# 3phasecntrl-rev2.net
KiCad netlist of a schematic drawn in EAGLE
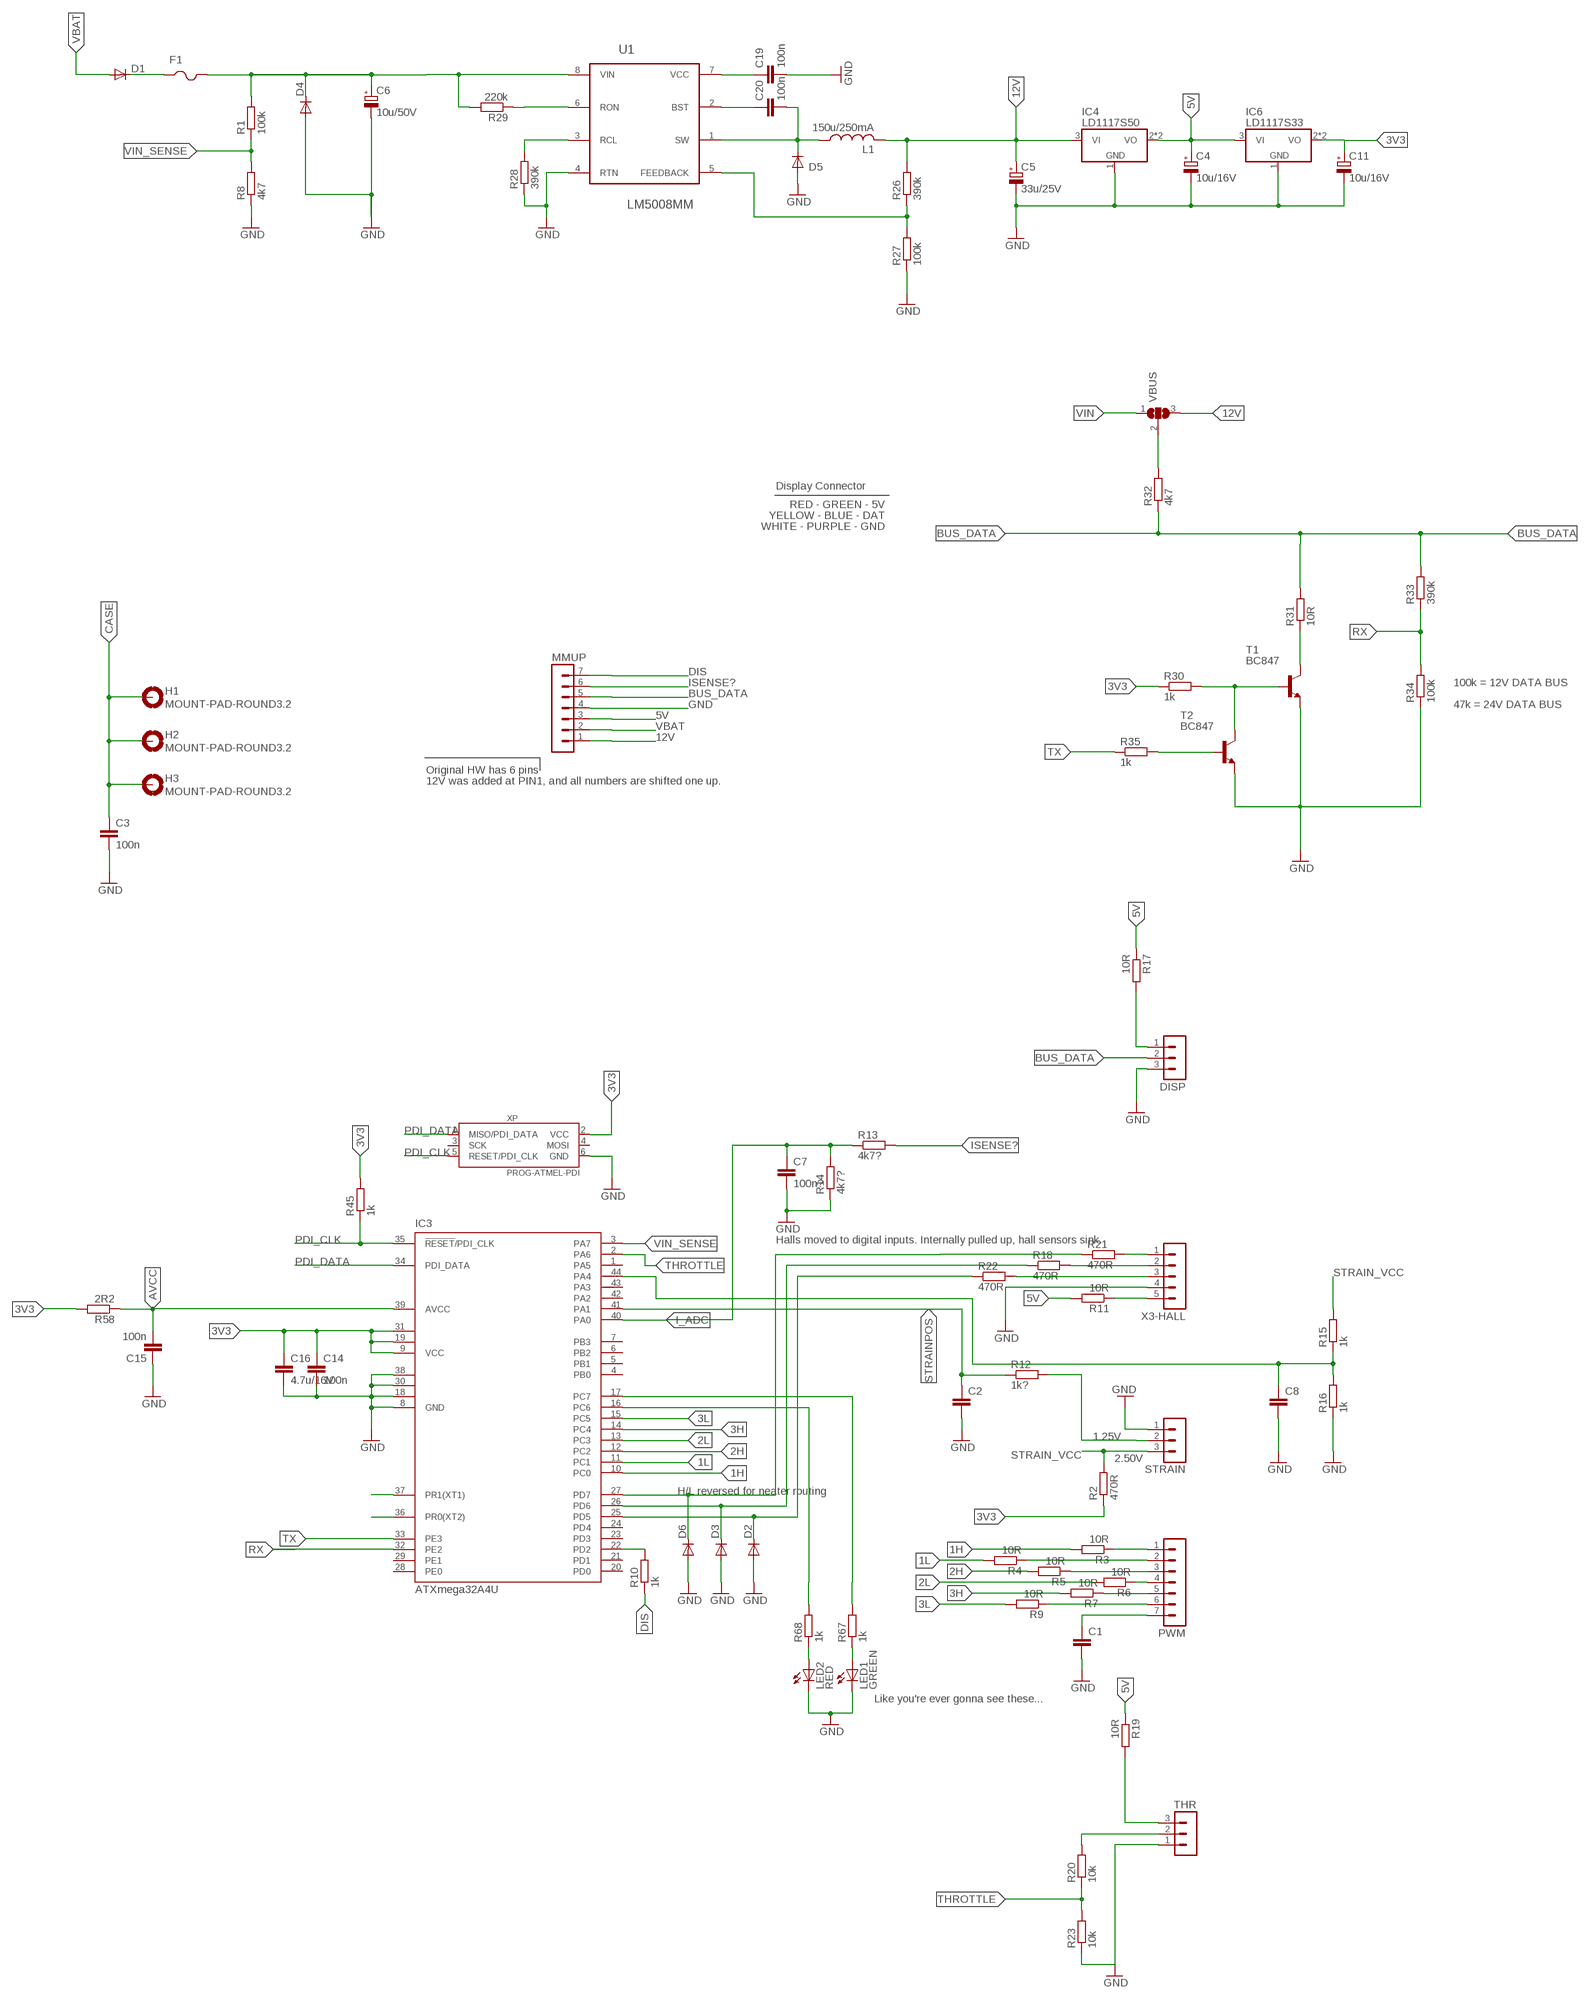
[diagram p0: schematic, sheet 1]

(export (version "E")
  (design (tool "Eeschema 10.0.6"))
  (components
    (comp (ref "C1")
      (value "C-EUC0805K")
      (footprint "eagle-import:C0805K")
      (libsource (lib "eagle-import") (part "C-EUC0805K"))
    )
    (comp (ref "C2")
      (value "C-EUC0805K")
      (footprint "eagle-import:C0805K")
      (libsource (lib "eagle-import") (part "C-EUC0805K"))
    )
    (comp (ref "C3")
      (value "100n")
      (footprint "eagle-import:C0805K")
      (libsource (lib "eagle-import") (part "C-EUC0805K"))
    )
    (comp (ref "C4")
      (value "10u/16V")
      (footprint "eagle-import:153CLV-0405")
      (libsource (lib "eagle-import") (part "CPOL-EU153CLV-0405"))
    )
    (comp (ref "C5")
      (value "33u/25V")
      (footprint "eagle-import:153CLV-0605")
      (libsource (lib "eagle-import") (part "CPOL-EU153CLV-0605"))
    )
    (comp (ref "C6")
      (value "10u/50V")
      (footprint "eagle-import:153CLV-0605")
      (libsource (lib "eagle-import") (part "CPOL-EU153CLV-0605"))
    )
    (comp (ref "C7")
      (value "100n?")
      (footprint "eagle-import:C0805K")
      (libsource (lib "eagle-import") (part "C-EUC0805K"))
    )
    (comp (ref "C8")
      (value "C-EUC0805K")
      (footprint "eagle-import:C0805K")
      (libsource (lib "eagle-import") (part "C-EUC0805K"))
    )
    (comp (ref "C11")
      (value "10u/16V")
      (footprint "eagle-import:153CLV-0405")
      (libsource (lib "eagle-import") (part "CPOL-EU153CLV-0405"))
    )
    (comp (ref "C14")
      (value "100n")
      (footprint "eagle-import:C0805K")
      (libsource (lib "eagle-import") (part "C-EUC0805K"))
    )
    (comp (ref "C15")
      (value "100n")
      (footprint "eagle-import:C0805K")
      (libsource (lib "eagle-import") (part "C-EUC0805K"))
    )
    (comp (ref "C16")
      (value "4.7u/16V")
      (footprint "eagle-import:C0805K")
      (libsource (lib "eagle-import") (part "C-EUC0805K"))
    )
    (comp (ref "C19")
      (value "100n")
      (footprint "eagle-import:C0805K")
      (libsource (lib "eagle-import") (part "C-EUC0805K"))
    )
    (comp (ref "C20")
      (value "100n")
      (footprint "eagle-import:C0805K")
      (libsource (lib "eagle-import") (part "C-EUC0805K"))
    )
    (comp (ref "D1")
      (value "BAT46WH")
      (footprint "eagle-import:SMB")
      (libsource (lib "eagle-import") (part "DIODE-SMB"))
    )
    (comp (ref "D2")
      (value "PTVS3V3S1UTR")
      (footprint "eagle-import:SOD123")
      (libsource (lib "eagle-import") (part "DIODE-SOD123"))
    )
    (comp (ref "D3")
      (value "PTVS3V3S1UTR")
      (footprint "eagle-import:SOD123")
      (libsource (lib "eagle-import") (part "DIODE-SOD123"))
    )
    (comp (ref "D4")
      (value "SM6T39A")
      (footprint "eagle-import:SMB")
      (libsource (lib "eagle-import") (part "DIODE-SMB"))
    )
    (comp (ref "D5")
      (value "BAT46WH")
      (footprint "eagle-import:SOD323-W")
      (libsource (lib "eagle-import") (part "DIODE-SOD323-W"))
    )
    (comp (ref "D6")
      (value "PTVS3V3S1UTR")
      (footprint "eagle-import:SOD123")
      (libsource (lib "eagle-import") (part "DIODE-SOD123"))
    )
    (comp (ref "DISP")
      (value "MA03-1")
      (footprint "eagle-import:MA03-1")
      (fields (field (name "OC_FARNELL") "unknown") (field (name "OC_NEWARK") "unknown"))
      (libsource (lib "eagle-import") (part "MA03-1"))
    )
    (comp (ref "F1")
      (value "PTCFUSE-1812")
      (footprint "eagle-import:1812")
      (libsource (lib "eagle-import") (part "PTCFUSE-1812"))
    )
    (comp (ref "H1")
      (value "MOUNT-PAD-ROUND3.2")
      (footprint "eagle-import:3,2-PAD")
      (libsource (lib "eagle-import") (part "MOUNT-PAD-ROUND3.2"))
    )
    (comp (ref "H2")
      (value "MOUNT-PAD-ROUND3.2")
      (footprint "eagle-import:3,2-PAD")
      (libsource (lib "eagle-import") (part "MOUNT-PAD-ROUND3.2"))
    )
    (comp (ref "H3")
      (value "MOUNT-PAD-ROUND3.2")
      (footprint "eagle-import:3,2-PAD")
      (libsource (lib "eagle-import") (part "MOUNT-PAD-ROUND3.2"))
    )
    (comp (ref "IC3")
      (value "ATXmega32A4U")
      (footprint "eagle-import:TQFP44")
      (libsource (lib "eagle-import") (part "XMEGA16A4A"))
    )
    (comp (ref "IC4")
      (value "LD1117S50")
      (footprint "eagle-import:SOT223")
      (libsource (lib "eagle-import") (part "LM340?-STST"))
    )
    (comp (ref "IC6")
      (value "LD1117S33")
      (footprint "eagle-import:SOT223")
      (libsource (lib "eagle-import") (part "LM340?-STST"))
    )
    (comp (ref "L1")
      (value "150u/250mA")
      (footprint "eagle-import:POWER-CHOKE_WE-TPC")
      (libsource (lib "eagle-import") (part "L-USWE-TPC"))
    )
    (comp (ref "LED1")
      (value "GREEN")
      (footprint "eagle-import:CHIPLED_0805")
      (libsource (lib "eagle-import") (part "LEDCHIPLED_0805"))
    )
    (comp (ref "LED2")
      (value "RED")
      (footprint "eagle-import:CHIPLED_0805")
      (libsource (lib "eagle-import") (part "LEDCHIPLED_0805"))
    )
    (comp (ref "MMUP")
      (value "MA07-1")
      (footprint "eagle-import:MA07-1")
      (fields (field (name "OC_FARNELL") "unknown") (field (name "OC_NEWARK") "unknown"))
      (libsource (lib "eagle-import") (part "MA07-1"))
    )
    (comp (ref "PWM")
      (value "MA07-1")
      (footprint "eagle-import:MA07-1")
      (libsource (lib "eagle-import") (part "MA07-1"))
    )
    (comp (ref "R1")
      (value "100k")
      (footprint "eagle-import:M0805")
      (libsource (lib "eagle-import") (part "R-EU_M0805"))
    )
    (comp (ref "R2")
      (value "470R")
      (footprint "eagle-import:M0805")
      (libsource (lib "eagle-import") (part "R-EU_M0805"))
    )
    (comp (ref "R3")
      (value "10R")
      (footprint "eagle-import:M0805")
      (libsource (lib "eagle-import") (part "R-EU_M0805"))
    )
    (comp (ref "R4")
      (value "10R")
      (footprint "eagle-import:M0805")
      (libsource (lib "eagle-import") (part "R-EU_M0805"))
    )
    (comp (ref "R5")
      (value "10R")
      (footprint "eagle-import:M0805")
      (libsource (lib "eagle-import") (part "R-EU_M0805"))
    )
    (comp (ref "R6")
      (value "10R")
      (footprint "eagle-import:M0805")
      (libsource (lib "eagle-import") (part "R-EU_M0805"))
    )
    (comp (ref "R7")
      (value "10R")
      (footprint "eagle-import:M0805")
      (libsource (lib "eagle-import") (part "R-EU_M0805"))
    )
    (comp (ref "R8")
      (value "4k7")
      (footprint "eagle-import:M0805")
      (libsource (lib "eagle-import") (part "R-EU_M0805"))
    )
    (comp (ref "R9")
      (value "10R")
      (footprint "eagle-import:M0805")
      (libsource (lib "eagle-import") (part "R-EU_M0805"))
    )
    (comp (ref "R10")
      (value "1k")
      (footprint "eagle-import:M0805")
      (libsource (lib "eagle-import") (part "R-EU_M0805"))
    )
    (comp (ref "R11")
      (value "10R")
      (footprint "eagle-import:M0805")
      (libsource (lib "eagle-import") (part "R-EU_M0805"))
    )
    (comp (ref "R12")
      (value "1k?")
      (footprint "eagle-import:M0805")
      (libsource (lib "eagle-import") (part "R-EU_M0805"))
    )
    (comp (ref "R13")
      (value "4k7?")
      (footprint "eagle-import:M0805")
      (libsource (lib "eagle-import") (part "R-EU_M0805"))
    )
    (comp (ref "R14")
      (value "4k7?")
      (footprint "eagle-import:M0805")
      (libsource (lib "eagle-import") (part "R-EU_M0805"))
    )
    (comp (ref "R15")
      (value "1k")
      (footprint "eagle-import:M0805")
      (libsource (lib "eagle-import") (part "R-EU_M0805"))
    )
    (comp (ref "R16")
      (value "1k")
      (footprint "eagle-import:M0805")
      (libsource (lib "eagle-import") (part "R-EU_M0805"))
    )
    (comp (ref "R17")
      (value "10R")
      (footprint "eagle-import:M0805")
      (libsource (lib "eagle-import") (part "R-EU_M0805"))
    )
    (comp (ref "R18")
      (value "470R")
      (footprint "eagle-import:M0805")
      (libsource (lib "eagle-import") (part "R-EU_M0805"))
    )
    (comp (ref "R19")
      (value "10R")
      (footprint "eagle-import:M0805")
      (libsource (lib "eagle-import") (part "R-EU_M0805"))
    )
    (comp (ref "R20")
      (value "10k")
      (footprint "eagle-import:M0805")
      (libsource (lib "eagle-import") (part "R-EU_M0805"))
    )
    (comp (ref "R21")
      (value "470R")
      (footprint "eagle-import:M0805")
      (libsource (lib "eagle-import") (part "R-EU_M0805"))
    )
    (comp (ref "R22")
      (value "470R")
      (footprint "eagle-import:M0805")
      (libsource (lib "eagle-import") (part "R-EU_M0805"))
    )
    (comp (ref "R23")
      (value "10k")
      (footprint "eagle-import:M0805")
      (libsource (lib "eagle-import") (part "R-EU_M0805"))
    )
    (comp (ref "R26")
      (value "390k")
      (footprint "eagle-import:M0805")
      (libsource (lib "eagle-import") (part "R-EU_M0805"))
    )
    (comp (ref "R27")
      (value "100k")
      (footprint "eagle-import:M0805")
      (libsource (lib "eagle-import") (part "R-EU_M0805"))
    )
    (comp (ref "R28")
      (value "390k")
      (footprint "eagle-import:M0805")
      (libsource (lib "eagle-import") (part "R-EU_M0805"))
    )
    (comp (ref "R29")
      (value "220k")
      (footprint "eagle-import:M0805")
      (libsource (lib "eagle-import") (part "R-EU_M0805"))
    )
    (comp (ref "R30")
      (value "1k")
      (footprint "eagle-import:M0805")
      (libsource (lib "eagle-import") (part "R-EU_M0805"))
    )
    (comp (ref "R31")
      (value "10R")
      (footprint "eagle-import:M0805")
      (libsource (lib "eagle-import") (part "R-EU_M0805"))
    )
    (comp (ref "R32")
      (value "4k7")
      (footprint "eagle-import:M0805")
      (libsource (lib "eagle-import") (part "R-EU_M0805"))
    )
    (comp (ref "R33")
      (value "390k")
      (footprint "eagle-import:M0805")
      (libsource (lib "eagle-import") (part "R-EU_M0805"))
    )
    (comp (ref "R34")
      (value "100k")
      (footprint "eagle-import:M0805")
      (libsource (lib "eagle-import") (part "R-EU_M0805"))
    )
    (comp (ref "R35")
      (value "1k")
      (footprint "eagle-import:M0805")
      (libsource (lib "eagle-import") (part "R-EU_M0805"))
    )
    (comp (ref "R45")
      (value "1k")
      (footprint "eagle-import:R0805")
      (libsource (lib "eagle-import") (part "R-EU_R0805"))
    )
    (comp (ref "R58")
      (value "2R2")
      (footprint "eagle-import:R0805")
      (libsource (lib "eagle-import") (part "R-EU_R0805"))
    )
    (comp (ref "R67")
      (value "1k")
      (footprint "eagle-import:M0805")
      (libsource (lib "eagle-import") (part "R-EU_M0805"))
    )
    (comp (ref "R68")
      (value "1k")
      (footprint "eagle-import:M0805")
      (libsource (lib "eagle-import") (part "R-EU_M0805"))
    )
    (comp (ref "STRAIN")
      (value "MA03-1")
      (footprint "eagle-import:MA03-1")
      (libsource (lib "eagle-import") (part "MA03-1"))
    )
    (comp (ref "T1")
      (value "BC847")
      (footprint "eagle-import:SOT23")
      (libsource (lib "eagle-import") (part "BC847"))
    )
    (comp (ref "T2")
      (value "BC847")
      (footprint "eagle-import:SOT23")
      (libsource (lib "eagle-import") (part "BC847"))
    )
    (comp (ref "THR")
      (value "MA03-1")
      (footprint "eagle-import:MA03-1")
      (libsource (lib "eagle-import") (part "MA03-1"))
    )
    (comp (ref "U1")
      (value "LM5008MM")
      (footprint "eagle-import:SOP65P490X109-8N")
      (libsource (lib "eagle-import") (part "LM5008MM"))
    )
    (comp (ref "VBUS")
      (value "SJ2W")
      (footprint "eagle-import:SJ_2")
      (libsource (lib "eagle-import") (part "SJ2W"))
    )
    (comp (ref "X3-HALL")
      (value "MA05-1")
      (footprint "eagle-import:MA05-1")
      (libsource (lib "eagle-import") (part "MA05-1"))
    )
    (comp (ref "XP")
      (value "PROG-ATMEL-PDI")
      (footprint "eagle-import:6-LSTB2")
      (libsource (lib "eagle-import") (part "PROG-ATMEL-PDI"))
    )
  )
  (nets
    (net (code "1") (name "/PDI_CLK") (class "Default")
      (node (ref "IC3") (pin "35") (pinfunction "~{RESET}/PDI_CLK_35") (pintype "bidirectional"))
      (node (ref "R45") (pin "1") (pinfunction "1_1") (pintype "passive"))
      (node (ref "XP") (pin "5") (pinfunction "RESET/PDI_CLK_5") (pintype "bidirectional"))
    )
    (net (code "2") (name "/PDI_DATA") (class "Default")
      (node (ref "IC3") (pin "34") (pinfunction "PDI_DATA_34") (pintype "bidirectional"))
      (node (ref "XP") (pin "1") (pinfunction "MISO/PDI_DATA_1") (pintype "bidirectional"))
    )
    (net (code "3") (name "/STRAIN_VCC") (class "Default")
      (node (ref "R15") (pin "2") (pinfunction "2_2") (pintype "passive"))
      (node (ref "R2") (pin "2") (pinfunction "2_2") (pintype "passive"))
      (node (ref "STRAIN") (pin "3") (pinfunction "3_3") (pintype "passive"))
    )
    (net (code "4") (name "1H") (class "Default")
      (node (ref "IC3") (pin "10") (pinfunction "PC0_10") (pintype "bidirectional"))
      (node (ref "R3") (pin "2") (pinfunction "2_2") (pintype "passive"))
    )
    (net (code "5") (name "1L") (class "Default")
      (node (ref "IC3") (pin "11") (pinfunction "PC1_11") (pintype "bidirectional"))
      (node (ref "R4") (pin "2") (pinfunction "2_2") (pintype "passive"))
    )
    (net (code "6") (name "2H") (class "Default")
      (node (ref "IC3") (pin "12") (pinfunction "PC2_12") (pintype "bidirectional"))
      (node (ref "R5") (pin "2") (pinfunction "2_2") (pintype "passive"))
    )
    (net (code "7") (name "2L") (class "Default")
      (node (ref "IC3") (pin "13") (pinfunction "PC3_13") (pintype "bidirectional"))
      (node (ref "R6") (pin "2") (pinfunction "2_2") (pintype "passive"))
    )
    (net (code "8") (name "3H") (class "Default")
      (node (ref "IC3") (pin "14") (pinfunction "PC4_14") (pintype "bidirectional"))
      (node (ref "R7") (pin "2") (pinfunction "2_2") (pintype "passive"))
    )
    (net (code "9") (name "3L") (class "Default")
      (node (ref "IC3") (pin "15") (pinfunction "PC5_15") (pintype "bidirectional"))
      (node (ref "R9") (pin "2") (pinfunction "2_2") (pintype "passive"))
    )
    (net (code "10") (name "3V3") (class "Default")
      (node (ref "C11") (pin "+") (pinfunction "+_+") (pintype "passive"))
      (node (ref "C14") (pin "1") (pinfunction "1_1") (pintype "passive"))
      (node (ref "C16") (pin "1") (pinfunction "1_1") (pintype "passive"))
      (node (ref "IC3") (pin "19") (pinfunction "VCC1_19") (pintype "power_in"))
      (node (ref "IC3") (pin "31") (pinfunction "VCC2_31") (pintype "power_in"))
      (node (ref "IC3") (pin "9") (pinfunction "VCC_9") (pintype "power_in"))
      (node (ref "IC6") (pin "2") (pinfunction "VO_2") (pintype "passive"))
      (node (ref "IC6") (pin "4") (pinfunction "VO_4") (pintype "passive"))
      (node (ref "R2") (pin "1") (pinfunction "1_1") (pintype "passive"))
      (node (ref "R30") (pin "1") (pinfunction "1_1") (pintype "passive"))
      (node (ref "R45") (pin "2") (pinfunction "2_2") (pintype "passive"))
      (node (ref "R58") (pin "2") (pinfunction "2_2") (pintype "passive"))
      (node (ref "XP") (pin "2") (pinfunction "VCC_2") (pintype "bidirectional"))
    )
    (net (code "11") (name "5V") (class "Default")
      (node (ref "C4") (pin "+") (pinfunction "+_+") (pintype "passive"))
      (node (ref "IC4") (pin "2") (pinfunction "VO_2") (pintype "passive"))
      (node (ref "IC4") (pin "4") (pinfunction "VO_4") (pintype "passive"))
      (node (ref "IC6") (pin "3") (pinfunction "VI_3") (pintype "input"))
      (node (ref "MMUP") (pin "3") (pinfunction "3_3") (pintype "passive"))
      (node (ref "R11") (pin "2") (pinfunction "2_2") (pintype "passive"))
      (node (ref "R17") (pin "1") (pinfunction "1_1") (pintype "passive"))
      (node (ref "R19") (pin "1") (pinfunction "1_1") (pintype "passive"))
    )
    (net (code "12") (name "12V") (class "Default")
      (node (ref "C5") (pin "+") (pinfunction "+_+") (pintype "passive"))
      (node (ref "IC4") (pin "3") (pinfunction "VI_3") (pintype "input"))
      (node (ref "L1") (pin "2") (pinfunction "2_2") (pintype "passive"))
      (node (ref "MMUP") (pin "1") (pinfunction "1_1") (pintype "passive"))
      (node (ref "R26") (pin "2") (pinfunction "2_2") (pintype "passive"))
      (node (ref "VBUS") (pin "3") (pinfunction "3_3") (pintype "passive"))
    )
    (net (code "13") (name "AVCC") (class "Default")
      (node (ref "C15") (pin "2") (pinfunction "2_2") (pintype "passive"))
      (node (ref "IC3") (pin "39") (pinfunction "AVCC_39") (pintype "power_in"))
      (node (ref "R58") (pin "1") (pinfunction "1_1") (pintype "passive"))
    )
    (net (code "14") (name "BUS_DATA") (class "Default")
      (node (ref "DISP") (pin "2") (pinfunction "2_2") (pintype "passive"))
      (node (ref "MMUP") (pin "5") (pinfunction "5_5") (pintype "passive"))
      (node (ref "R31") (pin "2") (pinfunction "2_2") (pintype "passive"))
      (node (ref "R32") (pin "1") (pinfunction "1_1") (pintype "passive"))
      (node (ref "R33") (pin "2") (pinfunction "2_2") (pintype "passive"))
    )
    (net (code "15") (name "CASE") (class "Default")
      (node (ref "C3") (pin "1") (pinfunction "1_1") (pintype "passive"))
      (node (ref "H1") (pin "B3,2") (pinfunction "MOUNT_B3,2") (pintype "passive"))
      (node (ref "H2") (pin "B3,2") (pinfunction "MOUNT_B3,2") (pintype "passive"))
      (node (ref "H3") (pin "B3,2") (pinfunction "MOUNT_B3,2") (pintype "passive"))
    )
    (net (code "16") (name "DIS") (class "Default")
      (node (ref "MMUP") (pin "7") (pinfunction "7_7") (pintype "passive"))
      (node (ref "R10") (pin "1") (pinfunction "1_1") (pintype "passive"))
    )
    (net (code "17") (name "GND") (class "Default")
      (node (ref "C1") (pin "2") (pinfunction "2_2") (pintype "passive"))
      (node (ref "C11") (pin "-") (pinfunction "-_-") (pintype "passive"))
      (node (ref "C14") (pin "2") (pinfunction "2_2") (pintype "passive"))
      (node (ref "C15") (pin "1") (pinfunction "1_1") (pintype "passive"))
      (node (ref "C16") (pin "2") (pinfunction "2_2") (pintype "passive"))
      (node (ref "C19") (pin "2") (pinfunction "2_2") (pintype "passive"))
      (node (ref "C2") (pin "2") (pinfunction "2_2") (pintype "passive"))
      (node (ref "C3") (pin "2") (pinfunction "2_2") (pintype "passive"))
      (node (ref "C4") (pin "-") (pinfunction "-_-") (pintype "passive"))
      (node (ref "C5") (pin "-") (pinfunction "-_-") (pintype "passive"))
      (node (ref "C6") (pin "-") (pinfunction "-_-") (pintype "passive"))
      (node (ref "C7") (pin "2") (pinfunction "2_2") (pintype "passive"))
      (node (ref "C8") (pin "2") (pinfunction "2_2") (pintype "passive"))
      (node (ref "D2") (pin "A") (pinfunction "A_A") (pintype "passive"))
      (node (ref "D3") (pin "A") (pinfunction "A_A") (pintype "passive"))
      (node (ref "D4") (pin "A") (pinfunction "A_A") (pintype "passive"))
      (node (ref "D5") (pin "A") (pinfunction "A_A") (pintype "passive"))
      (node (ref "D6") (pin "A") (pinfunction "A_A") (pintype "passive"))
      (node (ref "DISP") (pin "3") (pinfunction "3_3") (pintype "passive"))
      (node (ref "IC3") (pin "18") (pinfunction "GND1_18") (pintype "power_in"))
      (node (ref "IC3") (pin "30") (pinfunction "GND2_30") (pintype "power_in"))
      (node (ref "IC3") (pin "38") (pinfunction "GND3_38") (pintype "power_in"))
      (node (ref "IC3") (pin "8") (pinfunction "GND_8") (pintype "power_in"))
      (node (ref "IC4") (pin "1") (pinfunction "GND_1") (pintype "passive"))
      (node (ref "IC6") (pin "1") (pinfunction "GND_1") (pintype "passive"))
      (node (ref "LED1") (pin "C") (pinfunction "C_C") (pintype "passive"))
      (node (ref "LED2") (pin "C") (pinfunction "C_C") (pintype "passive"))
      (node (ref "MMUP") (pin "4") (pinfunction "4_4") (pintype "passive"))
      (node (ref "R14") (pin "1") (pinfunction "1_1") (pintype "passive"))
      (node (ref "R16") (pin "1") (pinfunction "1_1") (pintype "passive"))
      (node (ref "R23") (pin "1") (pinfunction "1_1") (pintype "passive"))
      (node (ref "R27") (pin "1") (pinfunction "1_1") (pintype "passive"))
      (node (ref "R28") (pin "1") (pinfunction "1_1") (pintype "passive"))
      (node (ref "R34") (pin "1") (pinfunction "1_1") (pintype "passive"))
      (node (ref "R8") (pin "1") (pinfunction "1_1") (pintype "passive"))
      (node (ref "STRAIN") (pin "1") (pinfunction "1_1") (pintype "passive"))
      (node (ref "T1") (pin "2") (pinfunction "E_2") (pintype "passive"))
      (node (ref "T2") (pin "2") (pinfunction "E_2") (pintype "passive"))
      (node (ref "THR") (pin "1") (pinfunction "1_1") (pintype "passive"))
      (node (ref "U1") (pin "4") (pinfunction "RTN_4") (pintype "passive"))
      (node (ref "X3-HALL") (pin "4") (pinfunction "4_4") (pintype "passive"))
      (node (ref "XP") (pin "6") (pinfunction "GND_6") (pintype "bidirectional"))
    )
    (net (code "18") (name "ISENSE?") (class "Default")
      (node (ref "MMUP") (pin "6") (pinfunction "6_6") (pintype "passive"))
      (node (ref "R13") (pin "2") (pinfunction "2_2") (pintype "passive"))
    )
    (net (code "19") (name "I_ADC") (class "Default")
      (node (ref "C7") (pin "1") (pinfunction "1_1") (pintype "passive"))
      (node (ref "IC3") (pin "40") (pinfunction "PA0_40") (pintype "bidirectional"))
      (node (ref "R13") (pin "1") (pinfunction "1_1") (pintype "passive"))
      (node (ref "R14") (pin "2") (pinfunction "2_2") (pintype "passive"))
    )
    (net (code "20") (name "Net-(C1-Pad1)") (class "Default")
      (node (ref "C1") (pin "1") (pinfunction "1_1") (pintype "passive"))
      (node (ref "PWM") (pin "7") (pinfunction "7_7") (pintype "passive"))
    )
    (net (code "21") (name "Net-(D1-PadC)") (class "Default")
      (node (ref "D1") (pin "C") (pinfunction "C_C") (pintype "passive"))
      (node (ref "F1") (pin "1") (pinfunction "1_1") (pintype "passive"))
    )
    (net (code "22") (name "Net-(DISP-Pad1)") (class "Default")
      (node (ref "DISP") (pin "1") (pinfunction "1_1") (pintype "passive"))
      (node (ref "R17") (pin "2") (pinfunction "2_2") (pintype "passive"))
    )
    (net (code "23") (name "Net-(IC3-PA4)") (class "Default")
      (node (ref "C8") (pin "1") (pinfunction "1_1") (pintype "passive"))
      (node (ref "IC3") (pin "44") (pinfunction "PA4_44") (pintype "bidirectional"))
      (node (ref "R15") (pin "1") (pinfunction "1_1") (pintype "passive"))
      (node (ref "R16") (pin "2") (pinfunction "2_2") (pintype "passive"))
    )
    (net (code "24") (name "Net-(IC3-PC6)") (class "Default")
      (node (ref "IC3") (pin "16") (pinfunction "PC6_16") (pintype "bidirectional"))
      (node (ref "R68") (pin "2") (pinfunction "2_2") (pintype "passive"))
    )
    (net (code "25") (name "Net-(IC3-PC7)") (class "Default")
      (node (ref "IC3") (pin "17") (pinfunction "PC7_17") (pintype "bidirectional"))
      (node (ref "R67") (pin "2") (pinfunction "2_2") (pintype "passive"))
    )
    (net (code "26") (name "Net-(IC3-PD2)") (class "Default")
      (node (ref "IC3") (pin "22") (pinfunction "PD2_22") (pintype "bidirectional"))
      (node (ref "R10") (pin "2") (pinfunction "2_2") (pintype "passive"))
    )
    (net (code "27") (name "Net-(IC3-PD5)") (class "Default")
      (node (ref "D2") (pin "C") (pinfunction "C_C") (pintype "passive"))
      (node (ref "IC3") (pin "25") (pinfunction "PD5_25") (pintype "bidirectional"))
      (node (ref "R22") (pin "1") (pinfunction "1_1") (pintype "passive"))
    )
    (net (code "28") (name "Net-(IC3-PD6)") (class "Default")
      (node (ref "D3") (pin "C") (pinfunction "C_C") (pintype "passive"))
      (node (ref "IC3") (pin "26") (pinfunction "PD6_26") (pintype "bidirectional"))
      (node (ref "R18") (pin "1") (pinfunction "1_1") (pintype "passive"))
    )
    (net (code "29") (name "Net-(IC3-PD7)") (class "Default")
      (node (ref "D6") (pin "C") (pinfunction "C_C") (pintype "passive"))
      (node (ref "IC3") (pin "27") (pinfunction "PD7_27") (pintype "bidirectional"))
      (node (ref "R21") (pin "1") (pinfunction "1_1") (pintype "passive"))
    )
    (net (code "30") (name "Net-(LED1-PadA)") (class "Default")
      (node (ref "LED1") (pin "A") (pinfunction "A_A") (pintype "passive"))
      (node (ref "R67") (pin "1") (pinfunction "1_1") (pintype "passive"))
    )
    (net (code "31") (name "Net-(LED2-PadA)") (class "Default")
      (node (ref "LED2") (pin "A") (pinfunction "A_A") (pintype "passive"))
      (node (ref "R68") (pin "1") (pinfunction "1_1") (pintype "passive"))
    )
    (net (code "32") (name "Net-(PWM-Pad1)") (class "Default")
      (node (ref "PWM") (pin "1") (pinfunction "1_1") (pintype "passive"))
      (node (ref "R3") (pin "1") (pinfunction "1_1") (pintype "passive"))
    )
    (net (code "33") (name "Net-(PWM-Pad2)") (class "Default")
      (node (ref "PWM") (pin "2") (pinfunction "2_2") (pintype "passive"))
      (node (ref "R4") (pin "1") (pinfunction "1_1") (pintype "passive"))
    )
    (net (code "34") (name "Net-(PWM-Pad3)") (class "Default")
      (node (ref "PWM") (pin "3") (pinfunction "3_3") (pintype "passive"))
      (node (ref "R5") (pin "1") (pinfunction "1_1") (pintype "passive"))
    )
    (net (code "35") (name "Net-(PWM-Pad4)") (class "Default")
      (node (ref "PWM") (pin "4") (pinfunction "4_4") (pintype "passive"))
      (node (ref "R6") (pin "1") (pinfunction "1_1") (pintype "passive"))
    )
    (net (code "36") (name "Net-(PWM-Pad5)") (class "Default")
      (node (ref "PWM") (pin "5") (pinfunction "5_5") (pintype "passive"))
      (node (ref "R7") (pin "1") (pinfunction "1_1") (pintype "passive"))
    )
    (net (code "37") (name "Net-(PWM-Pad6)") (class "Default")
      (node (ref "PWM") (pin "6") (pinfunction "6_6") (pintype "passive"))
      (node (ref "R9") (pin "1") (pinfunction "1_1") (pintype "passive"))
    )
    (net (code "38") (name "Net-(R11-Pad1)") (class "Default")
      (node (ref "R11") (pin "1") (pinfunction "1_1") (pintype "passive"))
      (node (ref "X3-HALL") (pin "5") (pinfunction "5_5") (pintype "passive"))
    )
    (net (code "39") (name "Net-(R12-Pad2)") (class "Default")
      (node (ref "R12") (pin "2") (pinfunction "2_2") (pintype "passive"))
      (node (ref "STRAIN") (pin "2") (pinfunction "2_2") (pintype "passive"))
    )
    (net (code "40") (name "Net-(R18-Pad2)") (class "Default")
      (node (ref "R18") (pin "2") (pinfunction "2_2") (pintype "passive"))
      (node (ref "X3-HALL") (pin "2") (pinfunction "2_2") (pintype "passive"))
    )
    (net (code "41") (name "Net-(R19-Pad2)") (class "Default")
      (node (ref "R19") (pin "2") (pinfunction "2_2") (pintype "passive"))
      (node (ref "THR") (pin "3") (pinfunction "3_3") (pintype "passive"))
    )
    (net (code "42") (name "Net-(R20-Pad2)") (class "Default")
      (node (ref "R20") (pin "2") (pinfunction "2_2") (pintype "passive"))
      (node (ref "THR") (pin "2") (pinfunction "2_2") (pintype "passive"))
    )
    (net (code "43") (name "Net-(R21-Pad2)") (class "Default")
      (node (ref "R21") (pin "2") (pinfunction "2_2") (pintype "passive"))
      (node (ref "X3-HALL") (pin "1") (pinfunction "1_1") (pintype "passive"))
    )
    (net (code "44") (name "Net-(R22-Pad2)") (class "Default")
      (node (ref "R22") (pin "2") (pinfunction "2_2") (pintype "passive"))
      (node (ref "X3-HALL") (pin "3") (pinfunction "3_3") (pintype "passive"))
    )
    (net (code "45") (name "Net-(R32-Pad2)") (class "Default")
      (node (ref "R32") (pin "2") (pinfunction "2_2") (pintype "passive"))
      (node (ref "VBUS") (pin "2") (pinfunction "2_2") (pintype "passive"))
    )
    (net (code "46") (name "Net-(T1-B)") (class "Default")
      (node (ref "R30") (pin "2") (pinfunction "2_2") (pintype "passive"))
      (node (ref "T1") (pin "1") (pinfunction "B_1") (pintype "passive"))
      (node (ref "T2") (pin "3") (pinfunction "C_3") (pintype "passive"))
    )
    (net (code "47") (name "Net-(T1-C)") (class "Default")
      (node (ref "R31") (pin "1") (pinfunction "1_1") (pintype "passive"))
      (node (ref "T1") (pin "3") (pinfunction "C_3") (pintype "passive"))
    )
    (net (code "48") (name "Net-(T2-B)") (class "Default")
      (node (ref "R35") (pin "2") (pinfunction "2_2") (pintype "passive"))
      (node (ref "T2") (pin "1") (pinfunction "B_1") (pintype "passive"))
    )
    (net (code "49") (name "Net-(U1-BST)") (class "Default")
      (node (ref "C20") (pin "1") (pinfunction "1_1") (pintype "passive"))
      (node (ref "U1") (pin "2") (pinfunction "BST_2") (pintype "passive"))
    )
    (net (code "50") (name "Net-(U1-FEEDBACK)") (class "Default")
      (node (ref "R26") (pin "1") (pinfunction "1_1") (pintype "passive"))
      (node (ref "R27") (pin "2") (pinfunction "2_2") (pintype "passive"))
      (node (ref "U1") (pin "5") (pinfunction "FEEDBACK_5") (pintype "input"))
    )
    (net (code "51") (name "Net-(U1-RCL)") (class "Default")
      (node (ref "R28") (pin "2") (pinfunction "2_2") (pintype "passive"))
      (node (ref "U1") (pin "3") (pinfunction "RCL_3") (pintype "passive"))
    )
    (net (code "52") (name "Net-(U1-RON)") (class "Default")
      (node (ref "R29") (pin "1") (pinfunction "1_1") (pintype "passive"))
      (node (ref "U1") (pin "6") (pinfunction "RON_6") (pintype "input"))
    )
    (net (code "53") (name "Net-(U1-SW)") (class "Default")
      (node (ref "C20") (pin "2") (pinfunction "2_2") (pintype "passive"))
      (node (ref "D5") (pin "C") (pinfunction "C_C") (pintype "passive"))
      (node (ref "L1") (pin "1") (pinfunction "1_1") (pintype "passive"))
      (node (ref "U1") (pin "1") (pinfunction "SW_1") (pintype "output"))
    )
    (net (code "54") (name "Net-(U1-VCC)") (class "Default")
      (node (ref "C19") (pin "1") (pinfunction "1_1") (pintype "passive"))
      (node (ref "U1") (pin "7") (pinfunction "VCC_7") (pintype "power_in"))
    )
    (net (code "55") (name "RX") (class "Default")
      (node (ref "IC3") (pin "32") (pinfunction "PE2_32") (pintype "bidirectional"))
      (node (ref "R33") (pin "1") (pinfunction "1_1") (pintype "passive"))
      (node (ref "R34") (pin "2") (pinfunction "2_2") (pintype "passive"))
    )
    (net (code "56") (name "STRAINPOS") (class "Default")
      (node (ref "C2") (pin "1") (pinfunction "1_1") (pintype "passive"))
      (node (ref "IC3") (pin "41") (pinfunction "PA1_41") (pintype "bidirectional"))
      (node (ref "R12") (pin "1") (pinfunction "1_1") (pintype "passive"))
    )
    (net (code "57") (name "THROTTLE") (class "Default")
      (node (ref "IC3") (pin "2") (pinfunction "PA6_2") (pintype "bidirectional"))
      (node (ref "R20") (pin "1") (pinfunction "1_1") (pintype "passive"))
      (node (ref "R23") (pin "2") (pinfunction "2_2") (pintype "passive"))
    )
    (net (code "58") (name "TX") (class "Default")
      (node (ref "IC3") (pin "33") (pinfunction "PE3_33") (pintype "bidirectional"))
      (node (ref "R35") (pin "1") (pinfunction "1_1") (pintype "passive"))
    )
    (net (code "59") (name "VBAT") (class "Default")
      (node (ref "D1") (pin "A") (pinfunction "A_A") (pintype "passive"))
      (node (ref "MMUP") (pin "2") (pinfunction "2_2") (pintype "passive"))
    )
    (net (code "60") (name "VIN") (class "Default")
      (node (ref "C6") (pin "+") (pinfunction "+_+") (pintype "passive"))
      (node (ref "D4") (pin "C") (pinfunction "C_C") (pintype "passive"))
      (node (ref "F1") (pin "2") (pinfunction "2_2") (pintype "passive"))
      (node (ref "R1") (pin "2") (pinfunction "2_2") (pintype "passive"))
      (node (ref "R29") (pin "2") (pinfunction "2_2") (pintype "passive"))
      (node (ref "U1") (pin "8") (pinfunction "VIN_8") (pintype "power_in"))
      (node (ref "VBUS") (pin "1") (pinfunction "1_1") (pintype "passive"))
    )
    (net (code "61") (name "VIN_SENSE") (class "Default")
      (node (ref "IC3") (pin "3") (pinfunction "PA7_3") (pintype "bidirectional"))
      (node (ref "R1") (pin "1") (pinfunction "1_1") (pintype "passive"))
      (node (ref "R8") (pin "2") (pinfunction "2_2") (pintype "passive"))
    )
    (net (code "62") (name "unconnected-(IC3-PA2-Pad42)") (class "Default")
      (node (ref "IC3") (pin "42") (pinfunction "PA2_42") (pintype "bidirectional"))
    )
    (net (code "63") (name "unconnected-(IC3-PA3-Pad43)") (class "Default")
      (node (ref "IC3") (pin "43") (pinfunction "PA3_43") (pintype "bidirectional"))
    )
    (net (code "64") (name "unconnected-(IC3-PA5-Pad1)") (class "Default")
      (node (ref "IC3") (pin "1") (pinfunction "PA5_1") (pintype "bidirectional"))
    )
    (net (code "65") (name "unconnected-(IC3-PB0-Pad4)") (class "Default")
      (node (ref "IC3") (pin "4") (pinfunction "PB0_4") (pintype "bidirectional"))
    )
    (net (code "66") (name "unconnected-(IC3-PB1-Pad5)") (class "Default")
      (node (ref "IC3") (pin "5") (pinfunction "PB1_5") (pintype "bidirectional"))
    )
    (net (code "67") (name "unconnected-(IC3-PB2-Pad6)") (class "Default")
      (node (ref "IC3") (pin "6") (pinfunction "PB2_6") (pintype "bidirectional"))
    )
    (net (code "68") (name "unconnected-(IC3-PB3-Pad7)") (class "Default")
      (node (ref "IC3") (pin "7") (pinfunction "PB3_7") (pintype "bidirectional"))
    )
    (net (code "69") (name "unconnected-(IC3-PD0-Pad20)") (class "Default")
      (node (ref "IC3") (pin "20") (pinfunction "PD0_20") (pintype "bidirectional"))
    )
    (net (code "70") (name "unconnected-(IC3-PD1-Pad21)") (class "Default")
      (node (ref "IC3") (pin "21") (pinfunction "PD1_21") (pintype "bidirectional"))
    )
    (net (code "71") (name "unconnected-(IC3-PD3-Pad23)") (class "Default")
      (node (ref "IC3") (pin "23") (pinfunction "PD3_23") (pintype "bidirectional"))
    )
    (net (code "72") (name "unconnected-(IC3-PD4-Pad24)") (class "Default")
      (node (ref "IC3") (pin "24") (pinfunction "PD4_24") (pintype "bidirectional"))
    )
    (net (code "73") (name "unconnected-(IC3-PE0-Pad28)") (class "Default")
      (node (ref "IC3") (pin "28") (pinfunction "PE0_28") (pintype "bidirectional"))
    )
    (net (code "74") (name "unconnected-(IC3-PE1-Pad29)") (class "Default")
      (node (ref "IC3") (pin "29") (pinfunction "PE1_29") (pintype "bidirectional"))
    )
    (net (code "75") (name "unconnected-(IC3-PR0(XT2)-Pad36)") (class "Default")
      (node (ref "IC3") (pin "36") (pinfunction "PR0(XT2)_36") (pintype "bidirectional"))
    )
    (net (code "76") (name "unconnected-(IC3-PR1(XT1)-Pad37)") (class "Default")
      (node (ref "IC3") (pin "37") (pinfunction "PR1(XT1)_37") (pintype "bidirectional"))
    )
    (net (code "77") (name "unconnected-(XP-MOSI-Pad4)") (class "Default")
      (node (ref "XP") (pin "4") (pinfunction "MOSI_4") (pintype "bidirectional"))
    )
    (net (code "78") (name "unconnected-(XP-SCK-Pad3)") (class "Default")
      (node (ref "XP") (pin "3") (pinfunction "SCK_3") (pintype "bidirectional"))
    )
  )
)
